# final.net
KiCad netlist of a schematic drawn in EAGLE
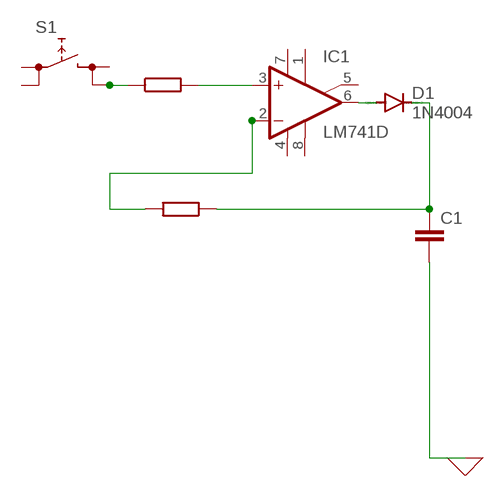
[diagram p0: schematic, sheet 1]

(export (version "E")
  (design (tool "Eeschema 10.0.6"))
  (components
    (comp (ref "C1")
      (value "C2.5/2")
      (footprint "eagle-import:C2.5-2")
      (libsource (lib "eagle-import") (part "C2.5/2"))
    )
    (comp (ref "D1")
      (value "1N4004")
      (footprint "eagle-import:DO41-10")
      (libsource (lib "eagle-import") (part "1N4004"))
    )
    (comp (ref "IC1")
      (value "LM741D")
      (footprint "eagle-import:SO08")
      (libsource (lib "eagle-import") (part "741DLM"))
    )
    (comp (ref "S1")
      (value "REKN")
      (footprint "eagle-import:REKN")
      (libsource (lib "eagle-import") (part "REKN"))
    )
  )
  (nets
    (net (code "1") (name "/V+") (class "Default")
      (node (ref "IC1") (pin "7") (pinfunction "V+_7") (pintype "power_in"))
    )
    (net (code "2") (name "/V-") (class "Default")
      (node (ref "IC1") (pin "4") (pinfunction "V-_4") (pintype "power_in"))
    )
    (net (code "3") (name "GND") (class "Default")
      (node (ref "C1") (pin "2") (pinfunction "2_2") (pintype "passive"))
    )
    (net (code "4") (name "Net-(C1-Pad1)") (class "Default")
      (node (ref "C1") (pin "1") (pinfunction "1_1") (pintype "passive"))
      (node (ref "D1") (pin "C") (pinfunction "C_C") (pintype "passive"))
    )
    (net (code "5") (name "Net-(IC1-OUT)") (class "Default")
      (node (ref "D1") (pin "A") (pinfunction "A_A") (pintype "passive"))
      (node (ref "IC1") (pin "6") (pinfunction "OUT_6") (pintype "output"))
    )
    (net (code "6") (name "unconnected-(IC1-+IN-Pad3)") (class "Default")
      (node (ref "IC1") (pin "3") (pinfunction "+IN_3") (pintype "input"))
    )
    (net (code "7") (name "unconnected-(IC1--IN-Pad2)") (class "Default")
      (node (ref "IC1") (pin "2") (pinfunction "-IN_2") (pintype "input"))
    )
    (net (code "8") (name "unconnected-(IC1-ON1-Pad1)") (class "Default")
      (node (ref "IC1") (pin "1") (pinfunction "ON1_1") (pintype "passive"))
    )
    (net (code "9") (name "unconnected-(IC1-ON2-Pad5)") (class "Default")
      (node (ref "IC1") (pin "5") (pinfunction "ON2_5") (pintype "passive"))
    )
    (net (code "10") (name "unconnected-(IC1-OPT-Pad8)") (class "Default")
      (node (ref "IC1") (pin "8") (pinfunction "OPT_8") (pintype "passive"))
    )
    (net (code "11") (name "unconnected-(S1-0-Pad0A)") (class "Default")
      (node (ref "S1") (pin "0A") (pinfunction "0_0A") (pintype "passive"))
    )
    (net (code "12") (name "unconnected-(S1-0-Pad0B)") (class "Default")
      (node (ref "S1") (pin "0B") (pinfunction "0_0B") (pintype "passive"))
    )
    (net (code "13") (name "unconnected-(S1-1-Pad1A)") (class "Default")
      (node (ref "S1") (pin "1A") (pinfunction "1_1A") (pintype "passive"))
    )
    (net (code "14") (name "unconnected-(S1-1-Pad1B)") (class "Default")
      (node (ref "S1") (pin "1B") (pinfunction "1_1B") (pintype "passive"))
    )
  )
)
